# UART.net
KiCad netlist of a schematic drawn in Altium Designer
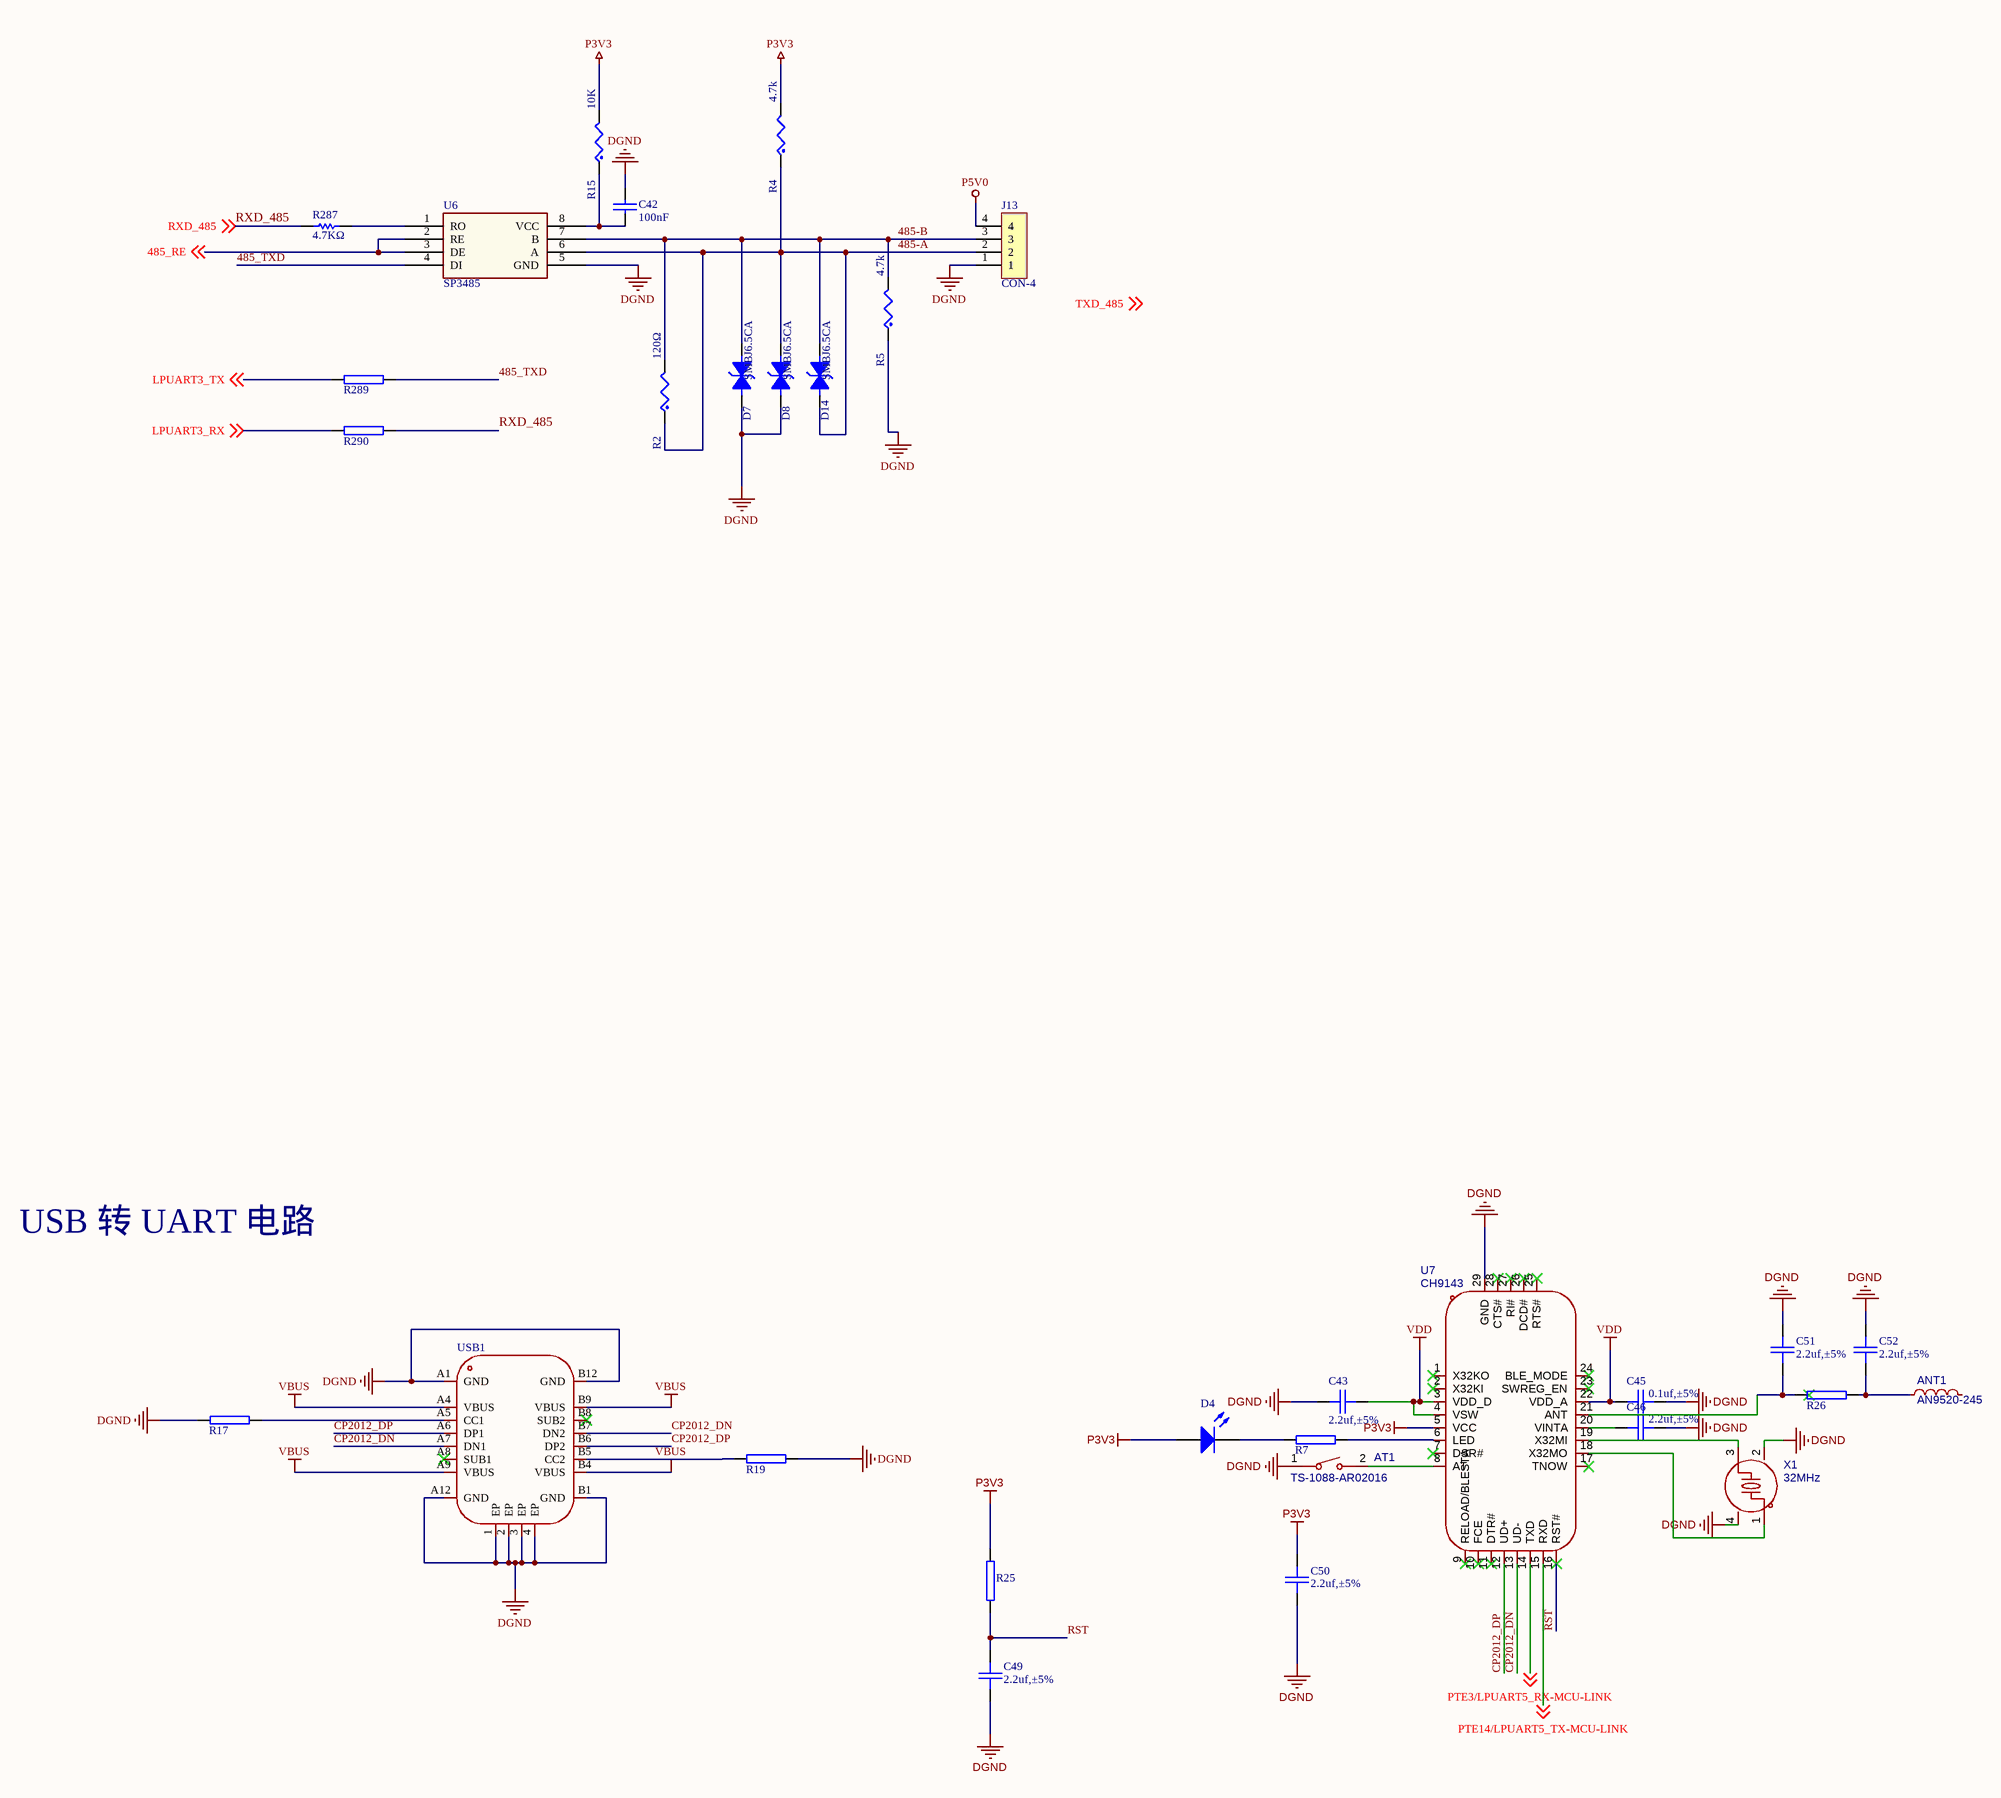
[diagram p0: UART.SchDoc]

(export (version "E")
  (design (tool "Eeschema 10.0.6"))
  (components
    (comp (ref "ANT1")
      (value "AN9520-245")
      (footprint "ANT-SMD_L9.5-W2.1")
      (description "2.4G陶瓷天线/适用于WIFI蓝牙")
      (fields (field (name "MANUFACTURER") "rainsun(霖昱微)"))
      (libsource (lib "altium-import") (part "root_0_AN9520-245_"))
    )
    (comp (ref "AT1")
      (value "TS-1088-AR02016")
      (footprint "SW-SMD_L3.9-W3.0-P4.45")
      (fields (field (name "MANUFACTURER") "XUNPU(讯普)"))
      (libsource (lib "altium-import") (part "root_0_TS-1088-AR02016_"))
    )
    (comp (ref "C42")
      (value "100nF")
      (footprint "CC0402_25")
      (description "Capacitor")
      (libsource (lib "TAG_ZYWB") (part "CAP"))
    )
    (comp (ref "C43")
      (value "2.2uf,±5%")
      (footprint "CC0402_25")
      (description "Capacitor")
      (libsource (lib "STM32F103C8T6+RC523") (part "CAP1"))
    )
    (comp (ref "C45")
      (value "0.1uf,±5%")
      (footprint "CC0402_25")
      (description "Capacitor")
      (libsource (lib "STM32F103C8T6+RC523") (part "CAP1"))
    )
    (comp (ref "C46")
      (value "2.2uf,±5%")
      (footprint "CC0402_25")
      (description "Capacitor")
      (libsource (lib "STM32F103C8T6+RC523") (part "CAP1"))
    )
    (comp (ref "C49")
      (value "2.2uf,±5%")
      (footprint "CC0402_25")
      (description "Capacitor")
      (libsource (lib "STM32F103C8T6+RC523") (part "CAP1"))
    )
    (comp (ref "C50")
      (value "2.2uf,±5%")
      (footprint "CC0402_25")
      (description "Capacitor")
      (libsource (lib "STM32F103C8T6+RC523") (part "CAP1"))
    )
    (comp (ref "C51")
      (value "2.2uf,±5%")
      (footprint "CC0402_25")
      (description "Capacitor")
      (libsource (lib "STM32F103C8T6+RC523") (part "CAP1"))
    )
    (comp (ref "C52")
      (value "2.2uf,±5%")
      (footprint "CC0402_25")
      (description "Capacitor")
      (libsource (lib "STM32F103C8T6+RC523") (part "CAP1"))
    )
    (comp (ref "D4")
      (value "~")
      (footprint "LED 0603R")
      (libsource (lib "MyMiscellaneousDevice") (part "LED-SMT"))
    )
    (comp (ref "D7") (value "SMBJ6.5CA") (footprint "1812") (libsource (lib "TAG_ZYWB") (part "BV05C")))
    (comp (ref "D8") (value "SMBJ6.5CA") (footprint "1812") (libsource (lib "TAG_ZYWB") (part "BV05C")))
    (comp (ref "D14") (value "SMBJ6.5CA") (footprint "1812") (libsource (lib "TAG_ZYWB") (part "BV05C")))
    (comp (ref "J13")
      (value "CON-4")
      (footprint "GSP003RC-4-3.5")
      (libsource (lib "所控显示20180528") (part "CON-4"))
    )
    (comp (ref "R2")
      (value "120Ω")
      (footprint "RC0603_OV")
      (description "RES MF ZERO OHM 1/10W -- 0603")
      (libsource (lib "*") (part "RES"))
    )
    (comp (ref "R4")
      (value "4.7k")
      (footprint "RC0603_OV")
      (description "RES MF ZERO OHM 1/10W -- 0603")
      (libsource (lib "*") (part "RES"))
    )
    (comp (ref "R5")
      (value "4.7k")
      (footprint "RC0603_OV")
      (description "RES MF ZERO OHM 1/10W -- 0603")
      (libsource (lib "*") (part "RES"))
    )
    (comp (ref "R7")
      (value "5k1")
      (footprint "RC0402_25")
      (libsource (lib "STM32F103C8T6+RC523") (part "RES2"))
    )
    (comp (ref "R15")
      (value "10K")
      (footprint "RC0603_OV")
      (description "RES MF ZERO OHM 1/10W -- 0603")
      (libsource (lib "*") (part "RES"))
    )
    (comp (ref "R17")
      (value "5k1")
      (footprint "RC0402_25")
      (libsource (lib "STM32F103C8T6+RC523") (part "RES2"))
    )
    (comp (ref "R19")
      (value "5k1")
      (footprint "RC0402_25")
      (libsource (lib "STM32F103C8T6+RC523") (part "RES2"))
    )
    (comp (ref "R25")
      (value "5k1")
      (footprint "RC0402_25")
      (libsource (lib "STM32F103C8T6+RC523") (part "RES2"))
    )
    (comp (ref "R26") (value "0") (footprint "0805R") (libsource (lib "STM32F103C8T6+RC523") (part "RES2")))
    (comp (ref "R287")
      (value "4.7KΩ")
      (footprint "R0402")
      (description "Resistor")
      (fields (field (name "PUBLISHER") "Altium Limited"))
      (libsource (lib "PCB_Project_1") (part "Res1"))
    )
    (comp (ref "R289")
      (value "0")
      (footprint "RC0402_25")
      (libsource (lib "STM32F103C8T6+RC523") (part "RES2"))
    )
    (comp (ref "R290")
      (value "0")
      (footprint "RC0402_25")
      (libsource (lib "STM32F103C8T6+RC523") (part "RES2"))
    )
    (comp (ref "U6") (value "SP3485") (footprint "SOP-8") (libsource (lib "TAG_ZYWB") (part "SP3485")))
    (comp (ref "U7")
      (value "CH9143")
      (footprint "QFN-28_L4.0-W4.0-P0.40-BL-EP2.7")
      (fields (field (name "MANUFACTURER") "WCH(南京沁恒)"))
      (libsource (lib "altium-import") (part "root_0_CH9143_"))
    )
    (comp (ref "USB1")
      (value "KH-TYPE-C-16P")
      (footprint "USB-C-SMD_KH-TYPE-C-16P")
      (description "连接器类型:Type-C;标准:-;公母:母;端口数量:1;触点数量:16P;安装方式:卧贴;额定电流 - 电源:3A;工作温度范围:-40℃~+85℃;")
      (fields (field (name "MANUFACTURER") "kinghelm(金航标)"))
      (libsource (lib "altium-import") (part "root_0_KH-TYPE-C-16P_"))
    )
    (comp (ref "X1")
      (value "32MHz")
      (footprint "CRYSTAL-SMD_4P-L2.0-W1.6-BL")
      (description "晶振类型:贴片晶振;频率:32MHz;常温频差:±10ppm;外接负载电容:8pF;频率稳定度(全温):±20ppm;")
      (fields
        (field (name "MANUFACTURER") "YXC(扬兴晶振)")
        (field (name "MANUFACTURER PART") "XL7EL89CKI-111YLC-32M")
      )
      (libsource (lib "altium-import") (part "root_1_XL7EL89CKI-111YLC-32M_"))
    )
  )
  (nets
    (net (code "1") (name "/485-A") (class "Default")
      (node (ref "D14") (pin "1") (pinfunction "CATHODE_1") (pintype "passive"))
      (node (ref "D8") (pin "2") (pinfunction "ANODE_2") (pintype "passive"))
      (node (ref "J13") (pin "2") (pinfunction "2_2") (pintype "passive"))
      (node (ref "R2") (pin "1") (pinfunction "1_1") (pintype "passive"))
      (node (ref "R4") (pin "1") (pinfunction "1_1") (pintype "passive"))
      (node (ref "U6") (pin "6") (pinfunction "A_6") (pintype "passive"))
    )
    (net (code "2") (name "/485-B") (class "Default")
      (node (ref "D14") (pin "2") (pinfunction "ANODE_2") (pintype "passive"))
      (node (ref "D7") (pin "2") (pinfunction "ANODE_2") (pintype "passive"))
      (node (ref "J13") (pin "3") (pinfunction "3_3") (pintype "passive"))
      (node (ref "R2") (pin "2") (pinfunction "2_2") (pintype "passive"))
      (node (ref "R5") (pin "2") (pinfunction "2_2") (pintype "passive"))
      (node (ref "U6") (pin "7") (pinfunction "B_7") (pintype "passive"))
    )
    (net (code "3") (name "/485_TXD") (class "Default")
      (node (ref "R289") (pin "1") (pinfunction "1_1") (pintype "passive"))
      (node (ref "U6") (pin "4") (pinfunction "DI_4") (pintype "passive"))
    )
    (net (code "4") (name "/CP2012_DN") (class "Default")
      (node (ref "U7") (pin "13") (pinfunction "UD-_13") (pintype "passive"))
      (node (ref "USB1") (pin "A7") (pinfunction "DN1_A7") (pintype "passive"))
      (node (ref "USB1") (pin "B7") (pinfunction "DN2_B7") (pintype "passive"))
    )
    (net (code "5") (name "/CP2012_DP") (class "Default")
      (node (ref "U7") (pin "12") (pinfunction "UD+_12") (pintype "passive"))
      (node (ref "USB1") (pin "A6") (pinfunction "DP1_A6") (pintype "passive"))
      (node (ref "USB1") (pin "B6") (pinfunction "DP2_B6") (pintype "passive"))
    )
    (net (code "6") (name "/RST") (class "Default")
      (node (ref "C49") (pin "2") (pinfunction "2_2") (pintype "passive"))
      (node (ref "R25") (pin "2") (pinfunction "2_2") (pintype "passive"))
      (node (ref "U7") (pin "16") (pinfunction "RST#_16") (pintype "passive"))
    )
    (net (code "7") (name "485_RE") (class "Default")
      (node (ref "U6") (pin "2") (pinfunction "RE_2") (pintype "passive"))
      (node (ref "U6") (pin "3") (pinfunction "DE_3") (pintype "passive"))
    )
    (net (code "8") (name "DGND") (class "Default")
      (node (ref "AT1") (pin "1") (pinfunction "1_1") (pintype "passive"))
      (node (ref "C42") (pin "2") (pinfunction "2_2") (pintype "passive"))
      (node (ref "C43") (pin "1") (pinfunction "1_1") (pintype "passive"))
      (node (ref "C45") (pin "2") (pinfunction "2_2") (pintype "passive"))
      (node (ref "C46") (pin "2") (pinfunction "2_2") (pintype "passive"))
      (node (ref "C49") (pin "1") (pinfunction "1_1") (pintype "passive"))
      (node (ref "C50") (pin "1") (pinfunction "1_1") (pintype "passive"))
      (node (ref "C51") (pin "2") (pinfunction "2_2") (pintype "passive"))
      (node (ref "C52") (pin "2") (pinfunction "2_2") (pintype "passive"))
      (node (ref "D7") (pin "1") (pinfunction "CATHODE_1") (pintype "passive"))
      (node (ref "D8") (pin "1") (pinfunction "CATHODE_1") (pintype "passive"))
      (node (ref "J13") (pin "1") (pinfunction "1_1") (pintype "passive"))
      (node (ref "R17") (pin "2") (pinfunction "2_2") (pintype "passive"))
      (node (ref "R19") (pin "1") (pinfunction "1_1") (pintype "passive"))
      (node (ref "R5") (pin "1") (pinfunction "1_1") (pintype "passive"))
      (node (ref "U6") (pin "5") (pinfunction "GND_5") (pintype "passive"))
      (node (ref "U7") (pin "29") (pinfunction "GND_29") (pintype "passive"))
      (node (ref "USB1") (pin "1") (pinfunction "EP_1") (pintype "passive"))
      (node (ref "USB1") (pin "2") (pinfunction "EP_2") (pintype "passive"))
      (node (ref "USB1") (pin "3") (pinfunction "EP_3") (pintype "passive"))
      (node (ref "USB1") (pin "4") (pinfunction "EP_4") (pintype "passive"))
      (node (ref "USB1") (pin "A1") (pinfunction "GND_A1") (pintype "passive"))
      (node (ref "USB1") (pin "A12") (pinfunction "GND_A12") (pintype "passive"))
      (node (ref "USB1") (pin "B1") (pinfunction "GND_B1") (pintype "passive"))
      (node (ref "USB1") (pin "B12") (pinfunction "GND_B12") (pintype "passive"))
      (node (ref "X1") (pin "2") (pinfunction "GND_2") (pintype "passive"))
      (node (ref "X1") (pin "4") (pinfunction "GND_4") (pintype "passive"))
    )
    (net (code "9") (name "LPUART3_RX") (class "Default")
      (node (ref "R290") (pin "2") (pinfunction "2_2") (pintype "passive"))
    )
    (net (code "10") (name "LPUART3_TX") (class "Default")
      (node (ref "R289") (pin "2") (pinfunction "2_2") (pintype "passive"))
    )
    (net (code "11") (name "Net-(ANT1-Pad1)") (class "Default")
      (node (ref "ANT1") (pin "1") (pinfunction "1_1") (pintype "passive"))
      (node (ref "C52") (pin "1") (pinfunction "1_1") (pintype "passive"))
      (node (ref "R26") (pin "1") (pinfunction "1_1") (pintype "passive"))
    )
    (net (code "12") (name "Net-(D4-K)") (class "Default")
      (node (ref "D4") (pin "2") (pinfunction "K_2") (pintype "passive"))
      (node (ref "R7") (pin "2") (pinfunction "2_2") (pintype "passive"))
    )
    (net (code "13") (name "Net-(U6-RO)") (class "Default")
      (node (ref "R287") (pin "1") (pinfunction "1_1") (pintype "passive"))
      (node (ref "U6") (pin "1") (pinfunction "RO_1") (pintype "passive"))
    )
    (net (code "14") (name "Net-(U6-VCC)") (class "Default")
      (node (ref "C42") (pin "1") (pinfunction "1_1") (pintype "passive"))
      (node (ref "R15") (pin "1") (pinfunction "1_1") (pintype "passive"))
      (node (ref "U6") (pin "8") (pinfunction "VCC_8") (pintype "passive"))
    )
    (net (code "15") (name "Net-(U7-ANT)") (class "Default")
      (node (ref "C51") (pin "1") (pinfunction "1_1") (pintype "passive"))
      (node (ref "R26") (pin "2") (pinfunction "2_2") (pintype "passive"))
      (node (ref "U7") (pin "21") (pinfunction "ANT_21") (pintype "passive"))
    )
    (net (code "16") (name "Net-(U7-AT)") (class "Default")
      (node (ref "AT1") (pin "2") (pinfunction "2_2") (pintype "passive"))
      (node (ref "U7") (pin "8") (pinfunction "AT_8") (pintype "passive"))
    )
    (net (code "17") (name "Net-(U7-LED)") (class "Default")
      (node (ref "R7") (pin "1") (pinfunction "1_1") (pintype "passive"))
      (node (ref "U7") (pin "6") (pinfunction "LED_6") (pintype "passive"))
    )
    (net (code "18") (name "Net-(U7-VINTA)") (class "Default")
      (node (ref "C46") (pin "1") (pinfunction "1_1") (pintype "passive"))
      (node (ref "U7") (pin "20") (pinfunction "VINTA_20") (pintype "passive"))
    )
    (net (code "19") (name "Net-(U7-X32MI)") (class "Default")
      (node (ref "U7") (pin "19") (pinfunction "X32MI_19") (pintype "passive"))
      (node (ref "X1") (pin "3") (pinfunction "3_3") (pintype "passive"))
    )
    (net (code "20") (name "Net-(U7-X32MO)") (class "Default")
      (node (ref "U7") (pin "18") (pinfunction "X32MO_18") (pintype "passive"))
      (node (ref "X1") (pin "1") (pinfunction "1_1") (pintype "passive"))
    )
    (net (code "21") (name "Net-(USB1-CC1)") (class "Default")
      (node (ref "R17") (pin "1") (pinfunction "1_1") (pintype "passive"))
      (node (ref "USB1") (pin "A5") (pinfunction "CC1_A5") (pintype "passive"))
    )
    (net (code "22") (name "Net-(USB1-CC2)") (class "Default")
      (node (ref "R19") (pin "2") (pinfunction "2_2") (pintype "passive"))
      (node (ref "USB1") (pin "B5") (pinfunction "CC2_B5") (pintype "passive"))
    )
    (net (code "23") (name "P3V3") (class "Default")
      (node (ref "C50") (pin "2") (pinfunction "2_2") (pintype "passive"))
      (node (ref "D4") (pin "1") (pinfunction "A_1") (pintype "passive"))
      (node (ref "R15") (pin "2") (pinfunction "2_2") (pintype "passive"))
      (node (ref "R25") (pin "1") (pinfunction "1_1") (pintype "passive"))
      (node (ref "R4") (pin "2") (pinfunction "2_2") (pintype "passive"))
      (node (ref "U7") (pin "5") (pinfunction "VCC_5") (pintype "passive"))
    )
    (net (code "24") (name "P5V0") (class "Default")
      (node (ref "J13") (pin "4") (pinfunction "4_4") (pintype "passive"))
    )
    (net (code "25") (name "PTE3{slash}LPUART5_RX-MCU-LINK") (class "Default")
      (node (ref "U7") (pin "14") (pinfunction "TXD_14") (pintype "passive"))
    )
    (net (code "26") (name "PTE14{slash}LPUART5_TX-MCU-LINK") (class "Default")
      (node (ref "U7") (pin "15") (pinfunction "RXD_15") (pintype "passive"))
    )
    (net (code "27") (name "RXD_485") (class "Default")
      (node (ref "R287") (pin "2") (pinfunction "2_2") (pintype "passive"))
      (node (ref "R290") (pin "1") (pinfunction "1_1") (pintype "passive"))
    )
    (net (code "29") (name "VBUS") (class "Default")
      (node (ref "USB1") (pin "A4") (pinfunction "VBUS_A4") (pintype "passive"))
      (node (ref "USB1") (pin "A9") (pinfunction "VBUS_A9") (pintype "passive"))
      (node (ref "USB1") (pin "B4") (pinfunction "VBUS_B4") (pintype "passive"))
      (node (ref "USB1") (pin "B9") (pinfunction "VBUS_B9") (pintype "passive"))
    )
    (net (code "30") (name "VDD") (class "Default")
      (node (ref "C43") (pin "2") (pinfunction "2_2") (pintype "passive"))
      (node (ref "C45") (pin "1") (pinfunction "1_1") (pintype "passive"))
      (node (ref "U7") (pin "22") (pinfunction "VDD_A_22") (pintype "passive"))
      (node (ref "U7") (pin "3") (pinfunction "VDD_D_3") (pintype "passive"))
      (node (ref "U7") (pin "4") (pinfunction "VSW_4") (pintype "passive"))
    )
    (net (code "31") (name "unconnected-(ANT1-Pad2)") (class "Default")
      (node (ref "ANT1") (pin "2") (pinfunction "2_2") (pintype "passive"))
    )
    (net (code "32") (name "unconnected-(U7-BLE_MODE-Pad24)") (class "Default")
      (node (ref "U7") (pin "24") (pinfunction "BLE_MODE_24") (pintype "passive+no_connect"))
    )
    (net (code "33") (name "unconnected-(U7-CTS#-Pad28)") (class "Default")
      (node (ref "U7") (pin "28") (pinfunction "CTS#_28") (pintype "passive+no_connect"))
    )
    (net (code "34") (name "unconnected-(U7-DCD#-Pad26)") (class "Default")
      (node (ref "U7") (pin "26") (pinfunction "DCD#_26") (pintype "passive+no_connect"))
    )
    (net (code "35") (name "unconnected-(U7-DSR#-Pad7)") (class "Default")
      (node (ref "U7") (pin "7") (pinfunction "DSR#_7") (pintype "passive+no_connect"))
    )
    (net (code "36") (name "unconnected-(U7-DTR#-Pad11)") (class "Default")
      (node (ref "U7") (pin "11") (pinfunction "DTR#_11") (pintype "passive+no_connect"))
    )
    (net (code "37") (name "unconnected-(U7-FCE-Pad10)") (class "Default")
      (node (ref "U7") (pin "10") (pinfunction "FCE_10") (pintype "passive+no_connect"))
    )
    (net (code "38") (name "unconnected-(U7-RELOAD{slash}BLESTA-Pad9)") (class "Default")
      (node (ref "U7") (pin "9") (pinfunction "RELOAD/BLESTA_9") (pintype "passive+no_connect"))
    )
    (net (code "39") (name "unconnected-(U7-RI#-Pad27)") (class "Default")
      (node (ref "U7") (pin "27") (pinfunction "RI#_27") (pintype "passive+no_connect"))
    )
    (net (code "40") (name "unconnected-(U7-RTS#-Pad25)") (class "Default")
      (node (ref "U7") (pin "25") (pinfunction "RTS#_25") (pintype "passive+no_connect"))
    )
    (net (code "41") (name "unconnected-(U7-SWREG_EN-Pad23)") (class "Default")
      (node (ref "U7") (pin "23") (pinfunction "SWREG_EN_23") (pintype "passive+no_connect"))
    )
    (net (code "42") (name "unconnected-(U7-TNOW-Pad17)") (class "Default")
      (node (ref "U7") (pin "17") (pinfunction "TNOW_17") (pintype "passive+no_connect"))
    )
    (net (code "43") (name "unconnected-(U7-X32KI-Pad2)") (class "Default")
      (node (ref "U7") (pin "2") (pinfunction "X32KI_2") (pintype "passive+no_connect"))
    )
    (net (code "44") (name "unconnected-(U7-X32KO-Pad1)") (class "Default")
      (node (ref "U7") (pin "1") (pinfunction "X32KO_1") (pintype "passive+no_connect"))
    )
    (net (code "45") (name "unconnected-(USB1-SUB1-PadA8)") (class "Default")
      (node (ref "USB1") (pin "A8") (pinfunction "SUB1_A8") (pintype "passive+no_connect"))
    )
    (net (code "46") (name "unconnected-(USB1-SUB2-PadB8)") (class "Default")
      (node (ref "USB1") (pin "B8") (pinfunction "SUB2_B8") (pintype "passive+no_connect"))
    )
  )
)
